# Latch.net
KiCad netlist of a schematic drawn in Altium Designer
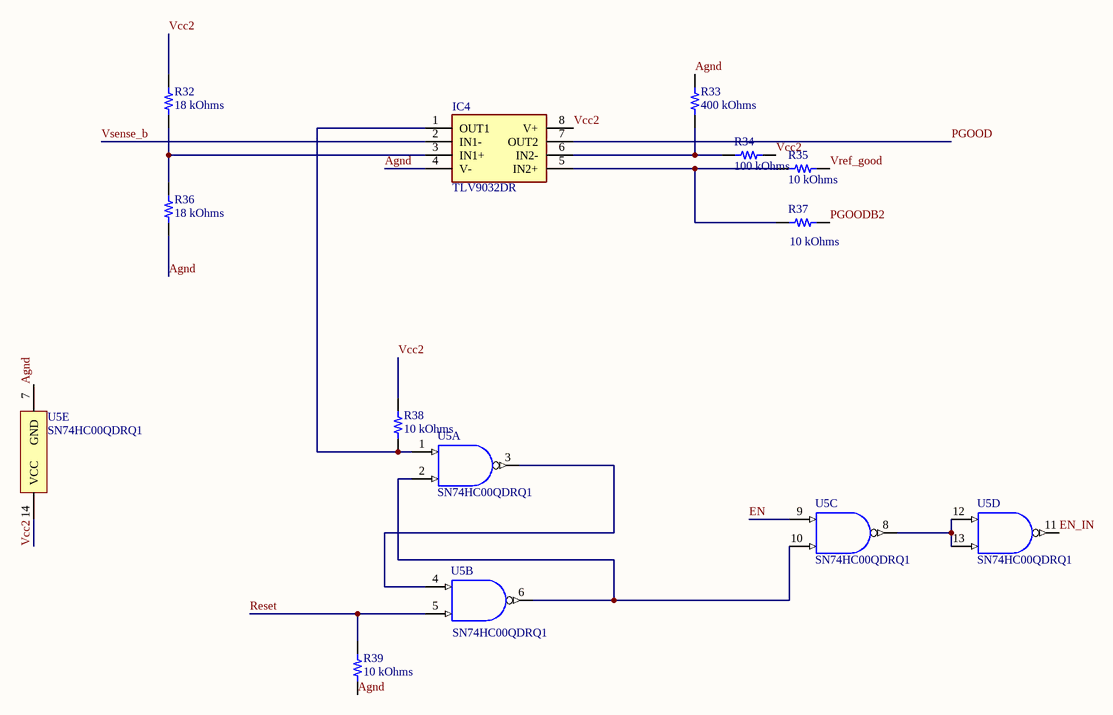
[diagram p0: Latch.SchDoc]

(export (version "E")
  (design (tool "Eeschema 10.0.6"))
  (components
    (comp (ref "IC4")
      (value "TLV9032DR")
      (footprint "SamacSys:SOIC127P600X175-8N")
      (description "Integrated Circuit")
      (fields (field (name "MOUSER PART NUMBER") "595-TLV9032DR"))
      (libsource (lib "*") (part "TLV9032DR"))
    )
    (comp (ref "R32")
      (value "18 kOhms")
      (footprint "RES 0603_1608")
      (description "RES SMD 18K OHM 0.1% 1/5W 0603")
      (fields
        (field (name "PART NUMBER") "ERJ-PB3B1802V")
        (field (name "MANUFACTURER") "Panasonic Electronic Components")
      )
      (libsource (lib "Celestial Altium Library - altium_library") (part "Resistor"))
    )
    (comp (ref "R33")
      (value "400 kOhms")
      (footprint "RES 0603_1608")
      (description "RES 1.5K OHM 1% 1/4W 0603")
      (fields
        (field (name "PART NUMBER") "CRGP0603F1K5")
        (field (name "MANUFACTURER") "TE Connectivity Passive Product")
      )
      (libsource (lib "Celestial Altium Library - altium_library") (part "Resistor"))
    )
    (comp (ref "R34")
      (value "100 kOhms")
      (footprint "RES 0603_1608")
      (description "RES 1.5K OHM 1% 1/4W 0603")
      (fields
        (field (name "PART NUMBER") "CRGP0603F1K5")
        (field (name "MANUFACTURER") "TE Connectivity Passive Product")
      )
      (libsource (lib "Celestial Altium Library - altium_library") (part "Resistor"))
    )
    (comp (ref "R35")
      (value "10 kOhms")
      (footprint "RES 0603_1608")
      (description "RES 1.5K OHM 1% 1/4W 0603")
      (fields
        (field (name "PART NUMBER") "CRGP0603F1K5")
        (field (name "MANUFACTURER") "TE Connectivity Passive Product")
      )
      (libsource (lib "Celestial Altium Library - altium_library") (part "Resistor"))
    )
    (comp (ref "R36")
      (value "18 kOhms")
      (footprint "RES 0603_1608")
      (description "RES SMD 18K OHM 0.1% 1/5W 0603")
      (fields
        (field (name "PART NUMBER") "ERJ-PB3B1802V")
        (field (name "MANUFACTURER") "Panasonic Electronic Components")
      )
      (libsource (lib "Celestial Altium Library - altium_library") (part "Resistor"))
    )
    (comp (ref "R37")
      (value "10 kOhms")
      (footprint "RES 0603_1608")
      (description "RES 1.5K OHM 1% 1/4W 0603")
      (fields
        (field (name "PART NUMBER") "CRGP0603F1K5")
        (field (name "MANUFACTURER") "TE Connectivity Passive Product")
      )
      (libsource (lib "Celestial Altium Library - altium_library") (part "Resistor"))
    )
    (comp (ref "R38")
      (value "10 kOhms")
      (footprint "RES 0603_1608")
      (description "RES 1.5K OHM 1% 1/4W 0603")
      (fields
        (field (name "PART NUMBER") "CRGP0603F1K5")
        (field (name "MANUFACTURER") "TE Connectivity Passive Product")
      )
      (libsource (lib "Celestial Altium Library - altium_library") (part "Resistor"))
    )
    (comp (ref "R39")
      (value "10 kOhms")
      (footprint "RES 0603_1608")
      (description "RES 1.5K OHM 1% 1/4W 0603")
      (fields
        (field (name "PART NUMBER") "CRGP0603F1K5")
        (field (name "MANUFACTURER") "TE Connectivity Passive Product")
      )
      (libsource (lib "Celestial Altium Library - altium_library") (part "Resistor"))
    )
    (comp (ref "U5")
      (value "SN74HC00QDRQ1")
      (footprint "D0014A_L")
      (description "Automotive Catalog Quad 2-Input Positive-NAND Gates, D0014A, LARGE T&R")
      (fields
        (field (name "MANUFACTURER") "Texas Instruments")
        (field (name "GENERIC PART NUMBER") "SN74HC00-Q1")
      )
      (libsource (lib "NANDfinal- 01.08.23 - 10.57") (part "CMP-1627-00175-2"))
    )
  )
  (nets
    (net (code "1") (name "/Agnd") (class "Default")
      (node (ref "IC4") (pin "4") (pinfunction "V-_4") (pintype "passive"))
      (node (ref "R33") (pin "1") (pinfunction "1_1") (pintype "passive"))
      (node (ref "R36") (pin "2") (pinfunction "2_2") (pintype "passive"))
      (node (ref "R39") (pin "2") (pinfunction "2_2") (pintype "passive"))
      (node (ref "U5") (pin "7") (pinfunction "GND_7") (pintype "power_in"))
    )
    (net (code "2") (name "/EN") (class "Default")
      (node (ref "U5") (pin "9") (pinfunction "3A_9") (pintype "input"))
    )
    (net (code "3") (name "/EN_IN") (class "Default")
      (node (ref "U5") (pin "11") (pinfunction "4Y_11") (pintype "output"))
    )
    (net (code "4") (name "/PGOOD") (class "Default")
      (node (ref "IC4") (pin "7") (pinfunction "OUT2_7") (pintype "passive"))
    )
    (net (code "5") (name "/PGOODB2") (class "Default")
      (node (ref "R37") (pin "1") (pinfunction "1_1") (pintype "passive"))
    )
    (net (code "6") (name "/Reset") (class "Default")
      (node (ref "R39") (pin "1") (pinfunction "1_1") (pintype "passive"))
      (node (ref "U5") (pin "5") (pinfunction "2B_5") (pintype "input"))
    )
    (net (code "7") (name "/Vcc2") (class "Default")
      (node (ref "IC4") (pin "8") (pinfunction "V+_8") (pintype "passive"))
      (node (ref "R32") (pin "1") (pinfunction "1_1") (pintype "passive"))
      (node (ref "R34") (pin "1") (pinfunction "1_1") (pintype "passive"))
      (node (ref "R38") (pin "1") (pinfunction "1_1") (pintype "passive"))
      (node (ref "U5") (pin "14") (pinfunction "VCC_14") (pintype "power_in"))
    )
    (net (code "8") (name "/Vref_good") (class "Default")
      (node (ref "R35") (pin "1") (pinfunction "1_1") (pintype "passive"))
    )
    (net (code "9") (name "/Vsense_b") (class "Default")
      (node (ref "IC4") (pin "2") (pinfunction "IN1-_2") (pintype "passive"))
    )
    (net (code "10") (name "Net-(IC4-IN1+)") (class "Default")
      (node (ref "IC4") (pin "3") (pinfunction "IN1+_3") (pintype "passive"))
      (node (ref "R32") (pin "2") (pinfunction "2_2") (pintype "passive"))
      (node (ref "R36") (pin "1") (pinfunction "1_1") (pintype "passive"))
    )
    (net (code "11") (name "Net-(IC4-IN2+)") (class "Default")
      (node (ref "IC4") (pin "5") (pinfunction "IN2+_5") (pintype "passive"))
      (node (ref "R35") (pin "2") (pinfunction "2_2") (pintype "passive"))
      (node (ref "R37") (pin "2") (pinfunction "2_2") (pintype "passive"))
    )
    (net (code "12") (name "Net-(IC4-IN2-)") (class "Default")
      (node (ref "IC4") (pin "6") (pinfunction "IN2-_6") (pintype "passive"))
      (node (ref "R33") (pin "2") (pinfunction "2_2") (pintype "passive"))
      (node (ref "R34") (pin "2") (pinfunction "2_2") (pintype "passive"))
    )
    (net (code "13") (name "Net-(IC4-OUT1)") (class "Default")
      (node (ref "IC4") (pin "1") (pinfunction "OUT1_1") (pintype "passive"))
      (node (ref "R38") (pin "2") (pinfunction "2_2") (pintype "passive"))
      (node (ref "U5") (pin "1") (pinfunction "1A_1") (pintype "input"))
    )
    (net (code "14") (name "Net-(U5A-1B)") (class "Default")
      (node (ref "U5") (pin "10") (pinfunction "3B_10") (pintype "input"))
      (node (ref "U5") (pin "2") (pinfunction "1B_2") (pintype "input"))
      (node (ref "U5") (pin "6") (pinfunction "2Y_6") (pintype "output"))
    )
    (net (code "15") (name "Net-(U5A-1Y)") (class "Default")
      (node (ref "U5") (pin "3") (pinfunction "1Y_3") (pintype "output"))
      (node (ref "U5") (pin "4") (pinfunction "2A_4") (pintype "input"))
    )
    (net (code "16") (name "Net-(U5C-3Y)") (class "Default")
      (node (ref "U5") (pin "12") (pinfunction "4A_12") (pintype "input"))
      (node (ref "U5") (pin "13") (pinfunction "4B_13") (pintype "input"))
      (node (ref "U5") (pin "8") (pinfunction "3Y_8") (pintype "output"))
    )
  )
)
